# Connector.net
KiCad netlist of a schematic drawn in Altium Designer
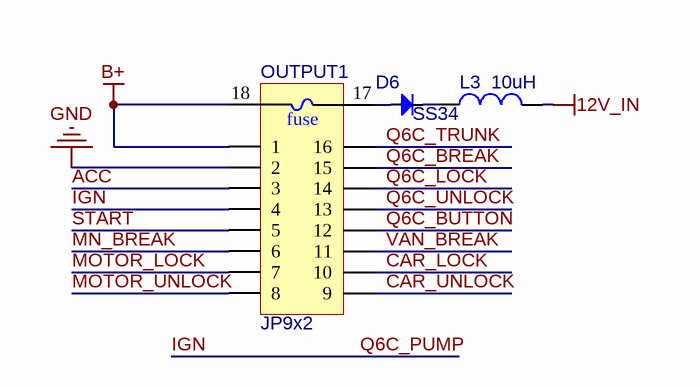
[diagram p0: Connector.SchDoc]

(export (version "E")
  (design (tool "Eeschema 10.0.6"))
  (components
    (comp (ref "D6")
      (value "SS34")
      (footprint "DIO-SMD-106")
      (description "Default Diode")
      (fields (field (name "PUBLISHER") "Altium Limited"))
      (libsource (lib "My Library") (part "Diode SMD"))
    )
    (comp (ref "L3")
      (value "10uH")
      (footprint "INDUCTOR_SMD_7X7MM")
      (description "Inductor")
      (libsource (lib "My Library") (part "Inductor_SMD"))
    )
    (comp (ref "OUTPUT1")
      (value "JP9x2")
      (footprint "9x2_JP200")
      (description "WR-PHD 2.54 mm Dual Socket Header")
      (fields
        (field (name "MANUFACTURER") "Würth Elektronik eiSos GmbH")
        (field (name "PARTNO") "61301821821")
        (field (name "CREATED BY") "Karrer Zheng")
      )
      (libsource (lib "My Library") (part "JP9x2_1"))
    )
  )
  (nets
    (net (code "1") (name "/ACC") (class "Default")
      (node (ref "OUTPUT1") (pin "3") (pinfunction "3_3") (pintype "passive"))
    )
    (net (code "2") (name "/CAR_LOCK") (class "Default")
      (node (ref "OUTPUT1") (pin "10") (pinfunction "10_10") (pintype "passive"))
    )
    (net (code "3") (name "/CAR_UNLOCK") (class "Default")
      (node (ref "OUTPUT1") (pin "9") (pinfunction "9_9") (pintype "passive"))
    )
    (net (code "4") (name "/IGN") (class "Default")
      (node (ref "OUTPUT1") (pin "4") (pinfunction "4_4") (pintype "passive"))
    )
    (net (code "5") (name "/MN_BREAK") (class "Default")
      (node (ref "OUTPUT1") (pin "6") (pinfunction "6_6") (pintype "passive"))
    )
    (net (code "6") (name "/MOTOR_LOCK") (class "Default")
      (node (ref "OUTPUT1") (pin "7") (pinfunction "7_7") (pintype "passive"))
    )
    (net (code "7") (name "/MOTOR_UNLOCK") (class "Default")
      (node (ref "OUTPUT1") (pin "8") (pinfunction "8_8") (pintype "passive"))
    )
    (net (code "8") (name "/Q6C_BREAK") (class "Default")
      (node (ref "OUTPUT1") (pin "15") (pinfunction "15_15") (pintype "passive"))
    )
    (net (code "9") (name "/Q6C_BUTTON") (class "Default")
      (node (ref "OUTPUT1") (pin "12") (pinfunction "12_12") (pintype "passive"))
    )
    (net (code "10") (name "/Q6C_LOCK") (class "Default")
      (node (ref "OUTPUT1") (pin "14") (pinfunction "14_14") (pintype "passive"))
    )
    (net (code "11") (name "/Q6C_TRUNK") (class "Default")
      (node (ref "OUTPUT1") (pin "16") (pinfunction "16_16") (pintype "passive"))
    )
    (net (code "12") (name "/Q6C_UNLOCK") (class "Default")
      (node (ref "OUTPUT1") (pin "13") (pinfunction "13_13") (pintype "passive"))
    )
    (net (code "13") (name "/START") (class "Default")
      (node (ref "OUTPUT1") (pin "5") (pinfunction "5_5") (pintype "passive"))
    )
    (net (code "14") (name "/VAN_BREAK") (class "Default")
      (node (ref "OUTPUT1") (pin "11") (pinfunction "11_11") (pintype "passive"))
    )
    (net (code "15") (name "12V_IN") (class "Default")
      (node (ref "L3") (pin "2") (pinfunction "2_2") (pintype "passive"))
    )
    (net (code "16") (name "B+") (class "Default")
      (node (ref "OUTPUT1") (pin "1") (pinfunction "1_1") (pintype "passive"))
      (node (ref "OUTPUT1") (pin "18") (pinfunction "18_18") (pintype "passive"))
    )
    (net (code "17") (name "GND") (class "Default")
      (node (ref "OUTPUT1") (pin "2") (pinfunction "2_2") (pintype "passive"))
    )
    (net (code "18") (name "Net-(D6-A)") (class "Default")
      (node (ref "D6") (pin "1") (pinfunction "A_1") (pintype "passive"))
      (node (ref "OUTPUT1") (pin "17") (pinfunction "17_17") (pintype "passive"))
    )
    (net (code "19") (name "Net-(D6-K)") (class "Default")
      (node (ref "D6") (pin "2") (pinfunction "K_2") (pintype "passive"))
      (node (ref "L3") (pin "1") (pinfunction "1_1") (pintype "passive"))
    )
  )
)
